# mainsche.net
KiCad netlist of a schematic drawn in Altium Designer
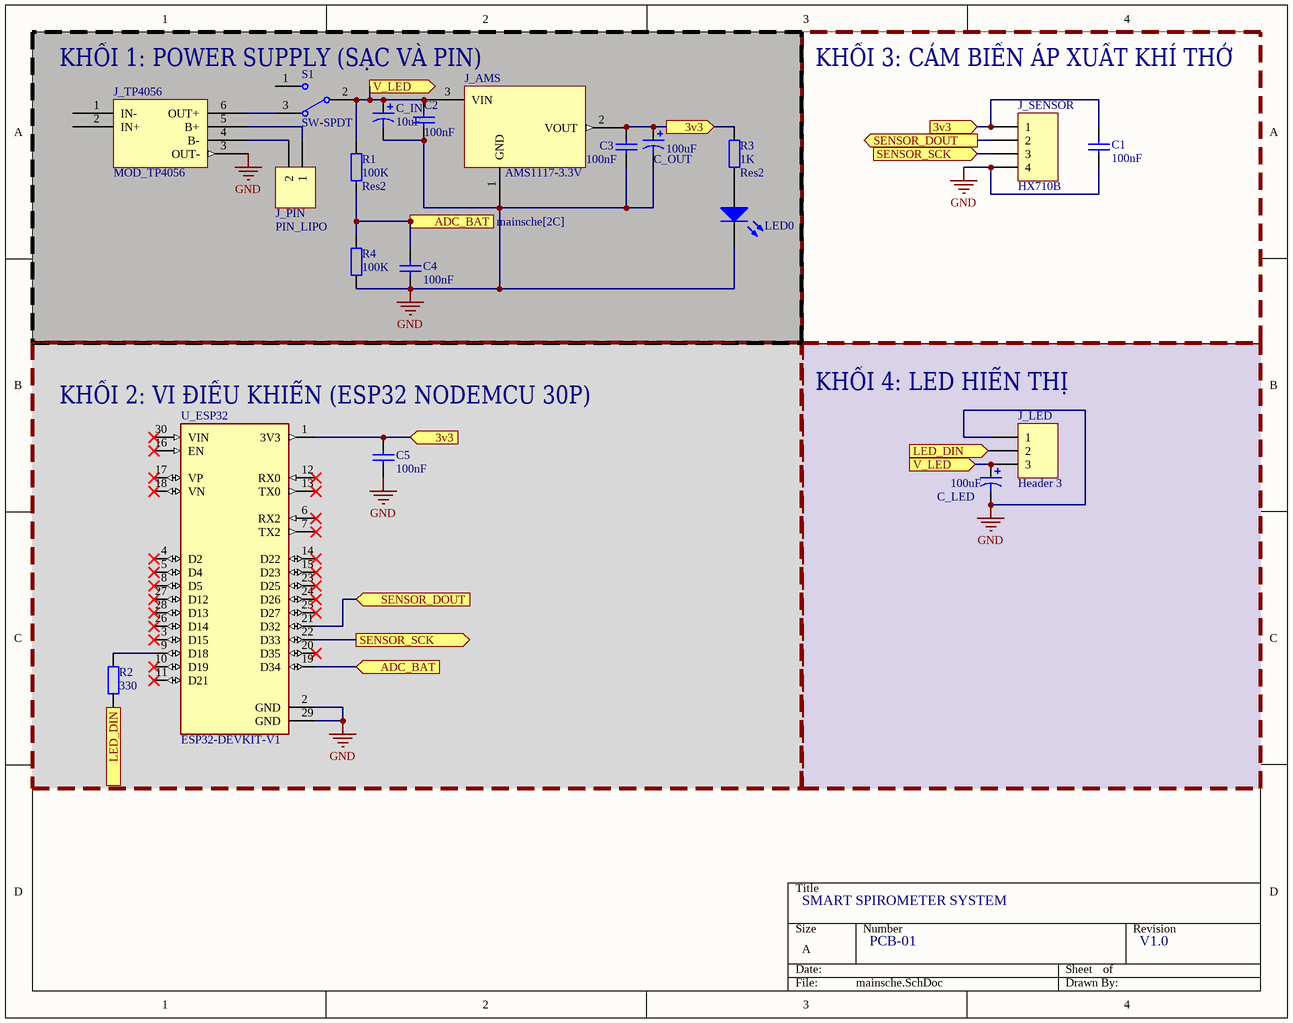
[diagram p0: mainsche.SchDoc]

(export (version "E")
  (design (tool "Eeschema 10.0.6"))
  (components
    (comp (ref "C1")
      (value "100nF")
      (footprint "RAD-0.2")
      (description "Capacitor")
      (fields (field (name "Comment") "Cap") (field (name "PUBLISHER") "Altium Limited"))
      (libsource (lib "Miscellaneous Devices") (part "Cap"))
    )
    (comp (ref "C2")
      (value "100nF")
      (footprint "RAD-0.2")
      (description "Capacitor")
      (fields (field (name "Comment") "Cap") (field (name "PUBLISHER") "Altium Limited"))
      (libsource (lib "Miscellaneous Devices") (part "Cap"))
    )
    (comp (ref "C3")
      (value "100nF")
      (footprint "RAD-0.2")
      (description "Capacitor")
      (fields (field (name "Comment") "Cap") (field (name "PUBLISHER") "Altium Limited"))
      (libsource (lib "Miscellaneous Devices") (part "Cap"))
    )
    (comp (ref "C4")
      (value "100nF")
      (footprint "RAD-0.2")
      (description "Capacitor")
      (fields (field (name "Comment") "Cap") (field (name "PUBLISHER") "Altium Limited"))
      (libsource (lib "Miscellaneous Devices") (part "Cap"))
    )
    (comp (ref "C5")
      (value "100nF")
      (footprint "RAD-0.2")
      (description "Capacitor")
      (fields (field (name "Comment") "Cap") (field (name "PUBLISHER") "Altium Limited"))
      (libsource (lib "Miscellaneous Devices") (part "Cap"))
    )
    (comp (ref "C_IN")
      (value "10uF")
      (footprint "RB5-10.5")
      (description "Polarized Capacitor (Radial)")
      (fields (field (name "Comment") "Cap Pol1") (field (name "PUBLISHER") "Altium Limited"))
      (libsource (lib "Miscellaneous Devices") (part "Cap Pol1"))
    )
    (comp (ref "C_LED")
      (value "100uF")
      (footprint "RB5-10.5")
      (description "Polarized Capacitor (Radial)")
      (fields (field (name "Comment") "Cap Pol1") (field (name "PUBLISHER") "Altium Limited"))
      (libsource (lib "Miscellaneous Devices") (part "Cap Pol1"))
    )
    (comp (ref "C_OUT")
      (value "100uF")
      (footprint "RB5-10.5")
      (description "Polarized Capacitor (Radial)")
      (fields (field (name "Comment") "Cap Pol1") (field (name "PUBLISHER") "Altium Limited"))
      (libsource (lib "Miscellaneous Devices") (part "Cap Pol1"))
    )
    (comp (ref "D1")
      (value "LED0")
      (footprint "LED-0")
      (description "Typical INFRARED GaAs LED")
      (fields (field (name "PUBLISHER") "Altium Limited"))
      (libsource (lib "Miscellaneous Devices") (part "LED0"))
    )
    (comp (ref "J_AMS")
      (value "AMS1117-3.3V")
      (footprint "SOT230P700X180-4M")
      (description "1A Fixed 3.3V 18V SOT-223 Voltage Regulators - Linear, Low Drop Out (LDO) Regulators ROHS")
      (libsource (lib "Dương Ngô") (part "AMS1117-3.3V-Symbol-1"))
    )
    (comp (ref "J_LED")
      (value "Header 3")
      (footprint "HDR1X3")
      (description "Header, 3-Pin")
      (fields (field (name "PUBLISHER") "Altium Limited"))
      (libsource (lib "Miscellaneous Connectors") (part "Header 3"))
    )
    (comp (ref "J_PIN")
      (value "PIN_LIPO")
      (footprint "HDR1X2")
      (description "Header, 2-Pin")
      (fields (field (name "PUBLISHER") "Altium Limited"))
      (libsource (lib "Miscellaneous Connectors") (part "Header 2"))
    )
    (comp (ref "J_SENSOR")
      (value "HX710B")
      (footprint "HDR1X4")
      (description "Header, 4-Pin")
      (fields (field (name "PUBLISHER") "Altium Limited"))
      (libsource (lib "Miscellaneous Connectors") (part "Header 4"))
    )
    (comp (ref "J_TP4056")
      (value "MOD_TP4056")
      (footprint "MOD_TP4056-Footprint-1")
      (libsource (lib "Dương Ngô") (part "MOD_TP4056-Symbol-1"))
    )
    (comp (ref "R1")
      (value "Res2")
      (footprint "AXIAL-0.3")
      (description "Resistor")
      (fields (field (name "ALTIUM_VALUE") "100K") (field (name "PUBLISHER") "Altium Limited"))
      (libsource (lib "Miscellaneous Devices") (part "Res2"))
    )
    (comp (ref "R2")
      (value "330")
      (footprint "AXIAL-0.3")
      (description "Resistor")
      (fields (field (name "Comment") "Res2") (field (name "PUBLISHER") "Altium Limited"))
      (libsource (lib "Miscellaneous Devices") (part "Res2"))
    )
    (comp (ref "R3")
      (value "Res2")
      (footprint "AXIAL-0.3")
      (description "Resistor")
      (fields (field (name "ALTIUM_VALUE") "1K") (field (name "PUBLISHER") "Altium Limited"))
      (libsource (lib "Miscellaneous Devices") (part "Res2"))
    )
    (comp (ref "R4")
      (value "100K")
      (footprint "AXIAL-0.3")
      (description "Resistor")
      (fields (field (name "Comment") "Res2") (field (name "PUBLISHER") "Altium Limited"))
      (libsource (lib "Miscellaneous Devices") (part "Res2"))
    )
    (comp (ref "S1")
      (value "SW-SPDT")
      (footprint "HDR1X3")
      (description "SPDT Subminiature Toggle Switch, Right Angle Mounting, Vertical Actuation")
      (fields (field (name "PUBLISHER") "Altium Limited"))
      (libsource (lib "Miscellaneous Devices") (part "SW-SPDT"))
    )
    (comp (ref "U_ESP32")
      (value "ESP32-DEVKIT-V1")
      (footprint "MODULE_ESP32_DEVKIT_V1")
      (fields (field (name "MF") "Do it"))
      (libsource (lib "ESP32-DEVKIT-V1") (part "ESP32-DEVKIT-V1"))
    )
  )
  (nets
    (net (code "1") (name "/3v3") (class "Default")
      (node (ref "C1") (pin "2") (pinfunction "2_2") (pintype "passive"))
      (node (ref "C3") (pin "2") (pinfunction "2_2") (pintype "passive"))
      (node (ref "C5") (pin "2") (pinfunction "2_2") (pintype "passive"))
      (node (ref "C_OUT") (pin "1") (pinfunction "1_1") (pintype "passive"))
      (node (ref "J_AMS") (pin "2") (pinfunction "VOUT_2") (pintype "output"))
      (node (ref "J_SENSOR") (pin "1") (pinfunction "1_1") (pintype "passive"))
      (node (ref "R3") (pin "2") (pinfunction "2_2") (pintype "passive"))
      (node (ref "U_ESP32") (pin "1") (pinfunction "3V3_1") (pintype "output"))
    )
    (net (code "2") (name "/ADC_BAT") (class "Default")
      (node (ref "C4") (pin "2") (pinfunction "2_2") (pintype "passive"))
      (node (ref "R1") (pin "1") (pinfunction "1_1") (pintype "passive"))
      (node (ref "R4") (pin "2") (pinfunction "2_2") (pintype "passive"))
      (node (ref "U_ESP32") (pin "19") (pinfunction "D34_19") (pintype "bidirectional"))
    )
    (net (code "3") (name "/LED_DIN") (class "Default")
      (node (ref "J_LED") (pin "2") (pinfunction "2_2") (pintype "passive"))
      (node (ref "R2") (pin "1") (pinfunction "1_1") (pintype "passive"))
    )
    (net (code "4") (name "/SENSOR_DOUT") (class "Default")
      (node (ref "J_SENSOR") (pin "2") (pinfunction "2_2") (pintype "passive"))
      (node (ref "U_ESP32") (pin "21") (pinfunction "D32_21") (pintype "bidirectional"))
    )
    (net (code "5") (name "/SENSOR_SCK") (class "Default")
      (node (ref "J_SENSOR") (pin "3") (pinfunction "3_3") (pintype "passive"))
      (node (ref "U_ESP32") (pin "22") (pinfunction "D33_22") (pintype "bidirectional"))
    )
    (net (code "6") (name "/V_LED") (class "Default")
      (node (ref "C2") (pin "1") (pinfunction "1_1") (pintype "passive"))
      (node (ref "C_IN") (pin "1") (pinfunction "1_1") (pintype "passive"))
      (node (ref "C_LED") (pin "1") (pinfunction "1_1") (pintype "passive"))
      (node (ref "J_AMS") (pin "3") (pinfunction "VIN_3") (pintype "power_in"))
      (node (ref "J_LED") (pin "3") (pinfunction "3_3") (pintype "passive"))
      (node (ref "R1") (pin "2") (pinfunction "2_2") (pintype "passive"))
      (node (ref "S1") (pin "2") (pinfunction "2_2") (pintype "passive"))
    )
    (net (code "7") (name "GND") (class "Default")
      (node (ref "C1") (pin "1") (pinfunction "1_1") (pintype "passive"))
      (node (ref "C2") (pin "2") (pinfunction "2_2") (pintype "passive"))
      (node (ref "C3") (pin "1") (pinfunction "1_1") (pintype "passive"))
      (node (ref "C4") (pin "1") (pinfunction "1_1") (pintype "passive"))
      (node (ref "C5") (pin "1") (pinfunction "1_1") (pintype "passive"))
      (node (ref "C_IN") (pin "2") (pinfunction "2_2") (pintype "passive"))
      (node (ref "C_LED") (pin "2") (pinfunction "2_2") (pintype "passive"))
      (node (ref "C_OUT") (pin "2") (pinfunction "2_2") (pintype "passive"))
      (node (ref "D1") (pin "2") (pinfunction "K_2") (pintype "passive"))
      (node (ref "J_AMS") (pin "1") (pinfunction "GND_1") (pintype "power_in"))
      (node (ref "J_LED") (pin "1") (pinfunction "1_1") (pintype "passive"))
      (node (ref "J_SENSOR") (pin "4") (pinfunction "4_4") (pintype "passive"))
      (node (ref "J_TP4056") (pin "3") (pinfunction "OUT-_3") (pintype "output"))
      (node (ref "R4") (pin "1") (pinfunction "1_1") (pintype "passive"))
      (node (ref "U_ESP32") (pin "2") (pinfunction "GND_2") (pintype "power_in"))
      (node (ref "U_ESP32") (pin "29") (pinfunction "GND_29") (pintype "power_in"))
    )
    (net (code "8") (name "Net-(D1-A)") (class "Default")
      (node (ref "D1") (pin "1") (pinfunction "A_1") (pintype "passive"))
      (node (ref "R3") (pin "1") (pinfunction "1_1") (pintype "passive"))
    )
    (net (code "9") (name "Net-(J_TP4056-B+)") (class "Default")
      (node (ref "J_PIN") (pin "1") (pinfunction "1_1") (pintype "passive"))
      (node (ref "J_TP4056") (pin "5") (pinfunction "B+_5") (pintype "passive"))
    )
    (net (code "10") (name "Net-(J_TP4056-B-)") (class "Default")
      (node (ref "J_PIN") (pin "2") (pinfunction "2_2") (pintype "passive"))
      (node (ref "J_TP4056") (pin "4") (pinfunction "B-_4") (pintype "passive"))
    )
    (net (code "11") (name "Net-(J_TP4056-OUT+)") (class "Default")
      (node (ref "J_TP4056") (pin "6") (pinfunction "OUT+_6") (pintype "power_in"))
      (node (ref "S1") (pin "3") (pinfunction "3_3") (pintype "passive"))
    )
    (net (code "12") (name "Net-(U_ESP32-D18)") (class "Default")
      (node (ref "R2") (pin "2") (pinfunction "2_2") (pintype "passive"))
      (node (ref "U_ESP32") (pin "9") (pinfunction "D18_9") (pintype "bidirectional"))
    )
    (net (code "13") (name "unconnected-(J_TP4056-IN+-Pad2)") (class "Default")
      (node (ref "J_TP4056") (pin "2") (pinfunction "IN+_2") (pintype "power_in"))
    )
    (net (code "14") (name "unconnected-(J_TP4056-IN--Pad1)") (class "Default")
      (node (ref "J_TP4056") (pin "1") (pinfunction "IN-_1") (pintype "power_in"))
    )
    (net (code "15") (name "unconnected-(S1-Pad1)") (class "Default")
      (node (ref "S1") (pin "1") (pinfunction "1_1") (pintype "passive"))
    )
    (net (code "16") (name "unconnected-(U_ESP32-D2-Pad4)") (class "Default")
      (node (ref "U_ESP32") (pin "4") (pinfunction "D2_4") (pintype "bidirectional+no_connect"))
    )
    (net (code "17") (name "unconnected-(U_ESP32-D4-Pad5)") (class "Default")
      (node (ref "U_ESP32") (pin "5") (pinfunction "D4_5") (pintype "bidirectional+no_connect"))
    )
    (net (code "18") (name "unconnected-(U_ESP32-D5-Pad8)") (class "Default")
      (node (ref "U_ESP32") (pin "8") (pinfunction "D5_8") (pintype "bidirectional+no_connect"))
    )
    (net (code "19") (name "unconnected-(U_ESP32-D12-Pad27)") (class "Default")
      (node (ref "U_ESP32") (pin "27") (pinfunction "D12_27") (pintype "bidirectional+no_connect"))
    )
    (net (code "20") (name "unconnected-(U_ESP32-D13-Pad28)") (class "Default")
      (node (ref "U_ESP32") (pin "28") (pinfunction "D13_28") (pintype "bidirectional+no_connect"))
    )
    (net (code "21") (name "unconnected-(U_ESP32-D14-Pad26)") (class "Default")
      (node (ref "U_ESP32") (pin "26") (pinfunction "D14_26") (pintype "bidirectional+no_connect"))
    )
    (net (code "22") (name "unconnected-(U_ESP32-D15-Pad3)") (class "Default")
      (node (ref "U_ESP32") (pin "3") (pinfunction "D15_3") (pintype "bidirectional+no_connect"))
    )
    (net (code "23") (name "unconnected-(U_ESP32-D19-Pad10)") (class "Default")
      (node (ref "U_ESP32") (pin "10") (pinfunction "D19_10") (pintype "bidirectional+no_connect"))
    )
    (net (code "24") (name "unconnected-(U_ESP32-D21-Pad11)") (class "Default")
      (node (ref "U_ESP32") (pin "11") (pinfunction "D21_11") (pintype "bidirectional+no_connect"))
    )
    (net (code "25") (name "unconnected-(U_ESP32-D22-Pad14)") (class "Default")
      (node (ref "U_ESP32") (pin "14") (pinfunction "D22_14") (pintype "bidirectional+no_connect"))
    )
    (net (code "26") (name "unconnected-(U_ESP32-D23-Pad15)") (class "Default")
      (node (ref "U_ESP32") (pin "15") (pinfunction "D23_15") (pintype "bidirectional+no_connect"))
    )
    (net (code "27") (name "unconnected-(U_ESP32-D25-Pad23)") (class "Default")
      (node (ref "U_ESP32") (pin "23") (pinfunction "D25_23") (pintype "bidirectional+no_connect"))
    )
    (net (code "28") (name "unconnected-(U_ESP32-D26-Pad24)") (class "Default")
      (node (ref "U_ESP32") (pin "24") (pinfunction "D26_24") (pintype "bidirectional+no_connect"))
    )
    (net (code "29") (name "unconnected-(U_ESP32-D27-Pad25)") (class "Default")
      (node (ref "U_ESP32") (pin "25") (pinfunction "D27_25") (pintype "bidirectional+no_connect"))
    )
    (net (code "30") (name "unconnected-(U_ESP32-D35-Pad20)") (class "Default")
      (node (ref "U_ESP32") (pin "20") (pinfunction "D35_20") (pintype "bidirectional+no_connect"))
    )
    (net (code "31") (name "unconnected-(U_ESP32-EN-Pad16)") (class "Default")
      (node (ref "U_ESP32") (pin "16") (pinfunction "EN_16") (pintype "input+no_connect"))
    )
    (net (code "32") (name "unconnected-(U_ESP32-RX0-Pad12)") (class "Default")
      (node (ref "U_ESP32") (pin "12") (pinfunction "RX0_12") (pintype "input+no_connect"))
    )
    (net (code "33") (name "unconnected-(U_ESP32-RX2-Pad6)") (class "Default")
      (node (ref "U_ESP32") (pin "6") (pinfunction "RX2_6") (pintype "input+no_connect"))
    )
    (net (code "34") (name "unconnected-(U_ESP32-TX0-Pad13)") (class "Default")
      (node (ref "U_ESP32") (pin "13") (pinfunction "TX0_13") (pintype "output+no_connect"))
    )
    (net (code "35") (name "unconnected-(U_ESP32-TX2-Pad7)") (class "Default")
      (node (ref "U_ESP32") (pin "7") (pinfunction "TX2_7") (pintype "output+no_connect"))
    )
    (net (code "36") (name "unconnected-(U_ESP32-VIN-Pad30)") (class "Default")
      (node (ref "U_ESP32") (pin "30") (pinfunction "VIN_30") (pintype "input+no_connect"))
    )
    (net (code "37") (name "unconnected-(U_ESP32-VN-Pad18)") (class "Default")
      (node (ref "U_ESP32") (pin "18") (pinfunction "VN_18") (pintype "bidirectional+no_connect"))
    )
    (net (code "38") (name "unconnected-(U_ESP32-VP-Pad17)") (class "Default")
      (node (ref "U_ESP32") (pin "17") (pinfunction "VP_17") (pintype "bidirectional+no_connect"))
    )
  )
)
